# power-breakout.net
KiCad netlist of a schematic drawn in EAGLE
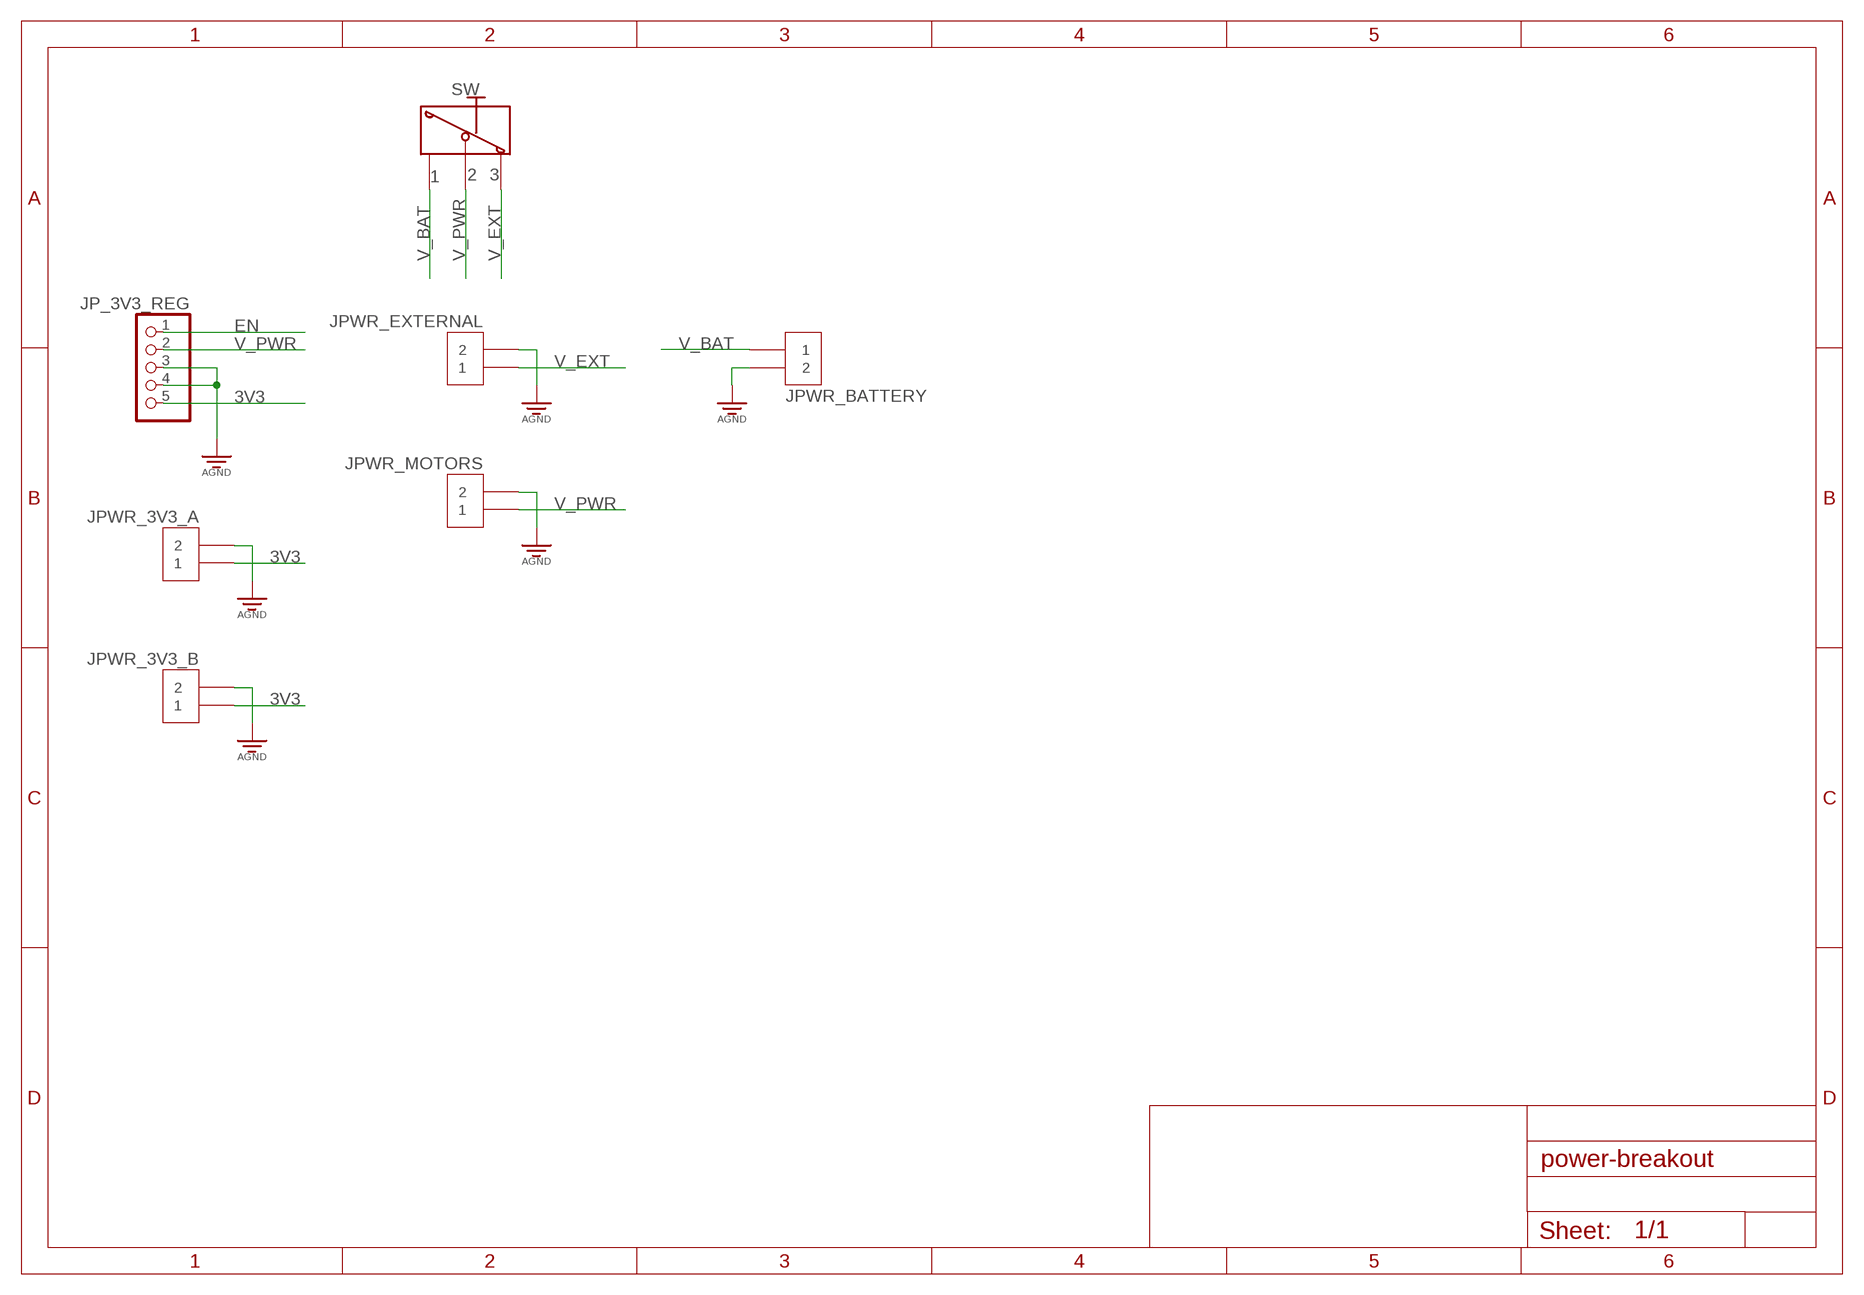
[diagram p0: schematic, sheet 1]

(export (version "E")
  (design (tool "Eeschema 10.0.6"))
  (components
    (comp (ref "JPWR_3V3_A")
      (value "WURTH_691103110002")
      (footprint "eagle-import:WURTH_691103110002")
      (libsource (lib "eagle-import") (part "WURTH_691103110002"))
    )
    (comp (ref "JPWR_3V3_B")
      (value "WURTH_691103110002")
      (footprint "eagle-import:WURTH_691103110002")
      (libsource (lib "eagle-import") (part "WURTH_691103110002"))
    )
    (comp (ref "JPWR_BATTERY")
      (value "WURTH_691103110002")
      (footprint "eagle-import:WURTH_691103110002")
      (libsource (lib "eagle-import") (part "WURTH_691103110002"))
    )
    (comp (ref "JPWR_EXTERNAL")
      (value "JST_B2P-VH_1X2_10A")
      (footprint "eagle-import:2_PINS,0.156_PITCH")
      (libsource (lib "eagle-import") (part "JST_B2P-VH_1X2_10A"))
    )
    (comp (ref "JPWR_MOTORS")
      (value "WURTH_691103110002")
      (footprint "eagle-import:WURTH_691103110002")
      (libsource (lib "eagle-import") (part "WURTH_691103110002"))
    )
    (comp (ref "JP_3V3_REG")
      (value "CON-1X5")
      (footprint "eagle-import:1X05-CONNECTOR")
      (libsource (lib "eagle-import") (part "CON-1X5"))
    )
    (comp (ref "SW")
      (value "APEM_GH39P0")
      (footprint "eagle-import:APEM_GH39P0")
      (libsource (lib "eagle-import") (part "APEM_GH39P0"))
    )
  )
  (nets
    (net (code "1") (name "/3V3") (class "Default")
      (node (ref "JPWR_3V3_A") (pin "1") (pinfunction "1_1") (pintype "passive"))
      (node (ref "JPWR_3V3_B") (pin "1") (pinfunction "1_1") (pintype "passive"))
      (node (ref "JP_3V3_REG") (pin "5") (pinfunction "5_5") (pintype "passive"))
    )
    (net (code "2") (name "/EN") (class "Default")
      (node (ref "JP_3V3_REG") (pin "1") (pinfunction "1_1") (pintype "passive"))
    )
    (net (code "3") (name "/V_BAT") (class "Default")
      (node (ref "JPWR_BATTERY") (pin "1") (pinfunction "1_1") (pintype "passive"))
      (node (ref "SW") (pin "P$1") (pinfunction "P$1_P$1") (pintype "bidirectional"))
    )
    (net (code "4") (name "/V_EXT") (class "Default")
      (node (ref "JPWR_EXTERNAL") (pin "1") (pinfunction "1_1") (pintype "passive"))
      (node (ref "SW") (pin "P$3") (pinfunction "P$3_P$3") (pintype "bidirectional"))
    )
    (net (code "5") (name "/V_PWR") (class "Default")
      (node (ref "JPWR_MOTORS") (pin "1") (pinfunction "1_1") (pintype "passive"))
      (node (ref "JP_3V3_REG") (pin "2") (pinfunction "2_2") (pintype "passive"))
      (node (ref "SW") (pin "P$2") (pinfunction "P$2_P$2") (pintype "bidirectional"))
    )
    (net (code "6") (name "AGND") (class "Default")
      (node (ref "JPWR_3V3_A") (pin "2") (pinfunction "2_2") (pintype "passive"))
      (node (ref "JPWR_3V3_B") (pin "2") (pinfunction "2_2") (pintype "passive"))
      (node (ref "JPWR_BATTERY") (pin "2") (pinfunction "2_2") (pintype "passive"))
      (node (ref "JPWR_EXTERNAL") (pin "2") (pinfunction "2_2") (pintype "passive"))
      (node (ref "JPWR_MOTORS") (pin "2") (pinfunction "2_2") (pintype "passive"))
      (node (ref "JP_3V3_REG") (pin "3") (pinfunction "3_3") (pintype "passive"))
      (node (ref "JP_3V3_REG") (pin "4") (pinfunction "4_4") (pintype "passive"))
    )
  )
)
